# WiFi_Turntable_Controller_v3.net
KiCad netlist of a schematic drawn in EAGLE
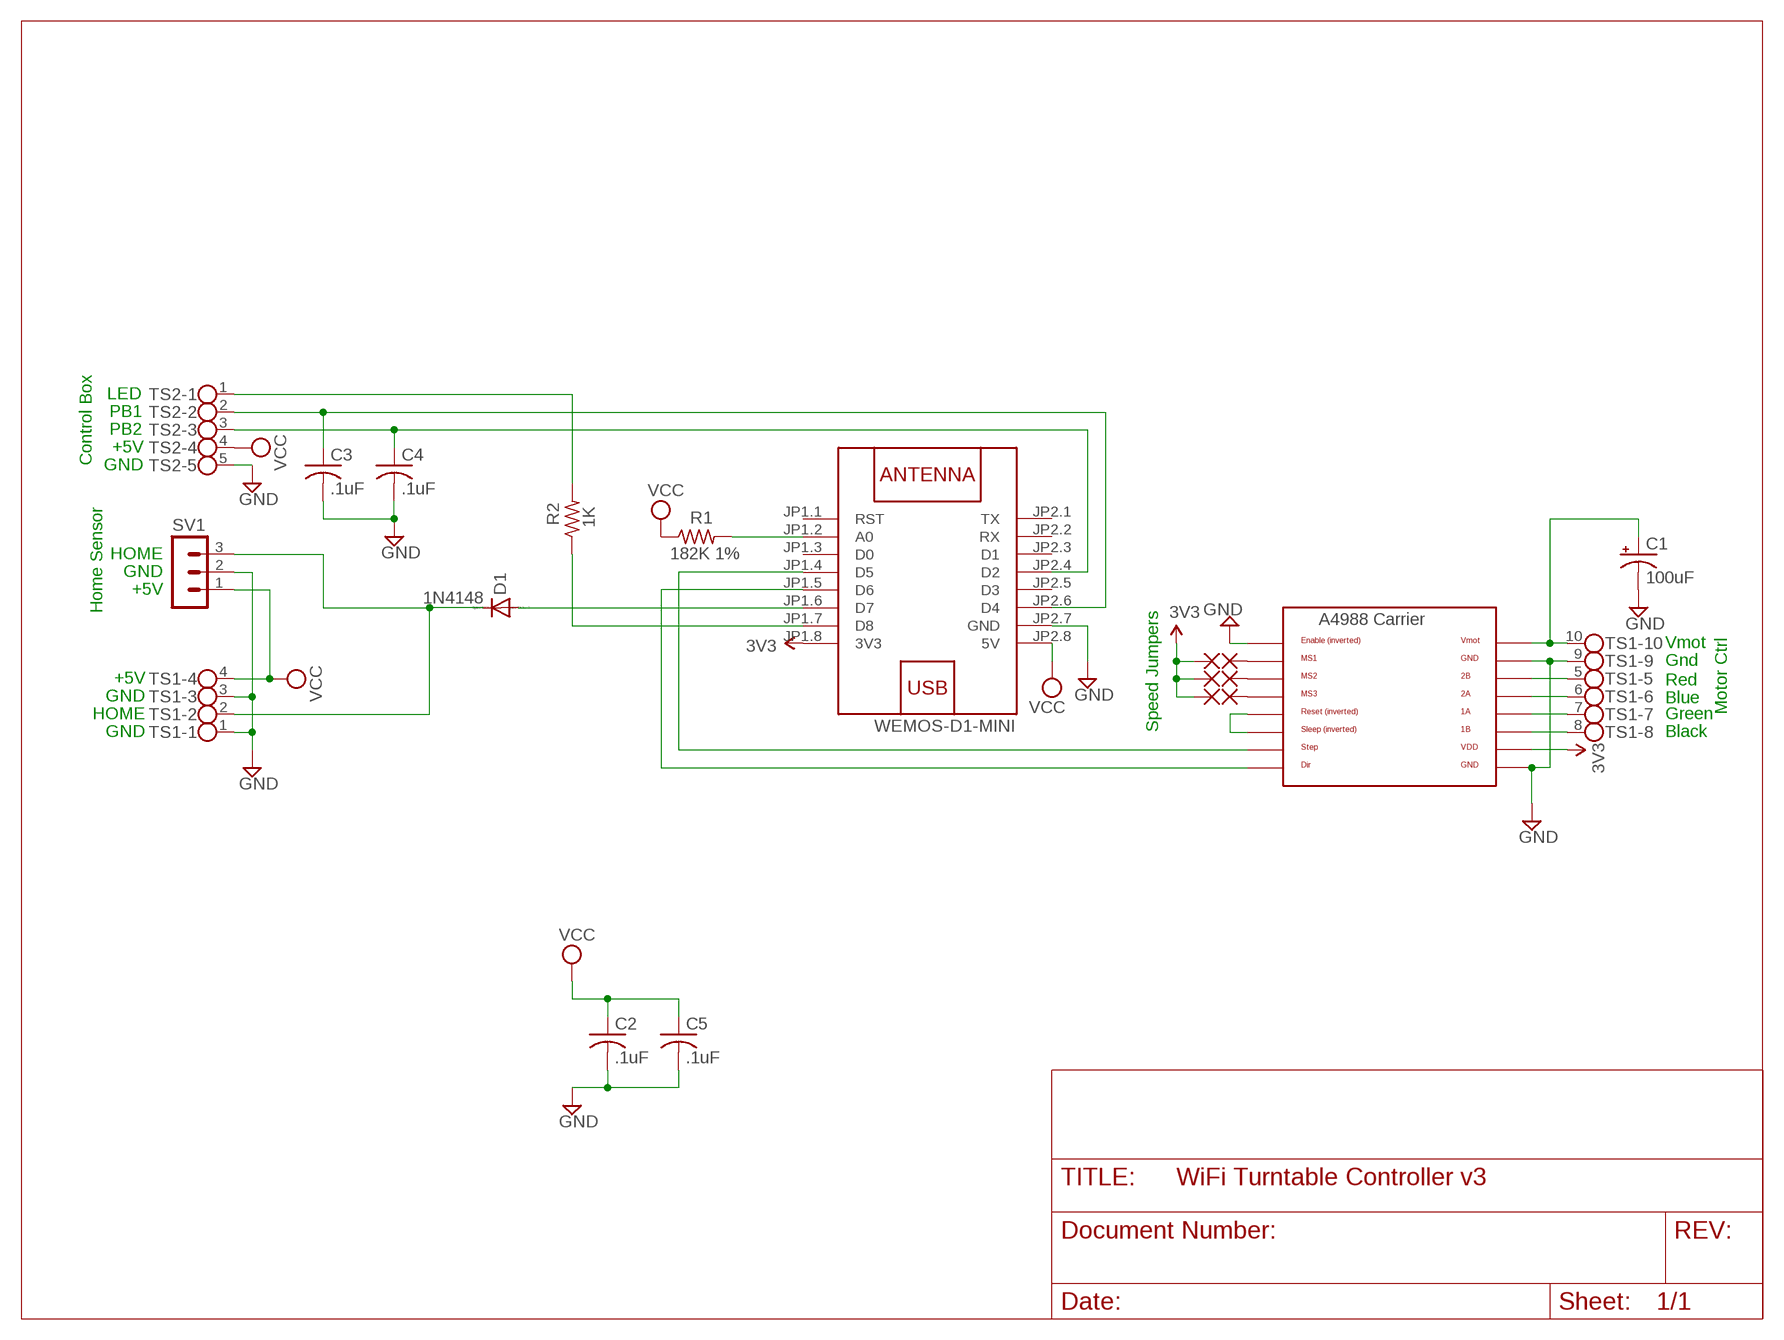
[diagram p0: schematic, sheet 1]

(export (version "E")
  (design (tool "Eeschema 10.0.6"))
  (components
    (comp (ref "C1")
      (value "100uF")
      (footprint "eagle-import:E3,5-8")
      (libsource (lib "eagle-import") (part "CPOL-USE3.5-8"))
    )
    (comp (ref "C2")
      (value ".1uF")
      (footprint "eagle-import:C1206")
      (libsource (lib "eagle-import") (part "C-USC1206"))
    )
    (comp (ref "C3")
      (value ".1uF")
      (footprint "eagle-import:C1206")
      (libsource (lib "eagle-import") (part "C-USC1206"))
    )
    (comp (ref "C4")
      (value ".1uF")
      (footprint "eagle-import:C1206")
      (libsource (lib "eagle-import") (part "C-USC1206"))
    )
    (comp (ref "C5")
      (value ".1uF")
      (footprint "eagle-import:C1206")
      (libsource (lib "eagle-import") (part "C-USC1206"))
    )
    (comp (ref "D1")
      (value "1N4148")
      (footprint "eagle-import:SOD123")
      (libsource (lib "eagle-import") (part "DIODE-SOD123"))
    )
    (comp (ref "PAD1")
      (value "1,6/0,8")
      (footprint "eagle-import:1,6_0,8")
      (libsource (lib "eagle-import") (part "1,6/0,8"))
    )
    (comp (ref "PAD2")
      (value "1,6/0,8")
      (footprint "eagle-import:1,6_0,8")
      (libsource (lib "eagle-import") (part "1,6/0,8"))
    )
    (comp (ref "PAD3")
      (value "1,6/0,8")
      (footprint "eagle-import:1,6_0,8")
      (libsource (lib "eagle-import") (part "1,6/0,8"))
    )
    (comp (ref "PAD4")
      (value "1,6/0,8")
      (footprint "eagle-import:1,6_0,8")
      (libsource (lib "eagle-import") (part "1,6/0,8"))
    )
    (comp (ref "PAD5")
      (value "1,6/0,8")
      (footprint "eagle-import:1,6_0,8")
      (libsource (lib "eagle-import") (part "1,6/0,8"))
    )
    (comp (ref "PAD6")
      (value "1,6/0,8")
      (footprint "eagle-import:1,6_0,8")
      (libsource (lib "eagle-import") (part "1,6/0,8"))
    )
    (comp (ref "R1")
      (value "182K 1%")
      (footprint "eagle-import:R1206")
      (libsource (lib "eagle-import") (part "R-US_R1206"))
    )
    (comp (ref "R2")
      (value "1K")
      (footprint "eagle-import:R1206")
      (libsource (lib "eagle-import") (part "R-US_R1206"))
    )
    (comp (ref "SV1")
      (value "MA03-1")
      (footprint "eagle-import:MA03-1")
      (libsource (lib "eagle-import") (part "MA03-1"))
    )
    (comp (ref "TS1")
      (value "TERMBLK10")
      (footprint "eagle-import:10PB")
      (libsource (lib "eagle-import") (part "TERMBLK10"))
    )
    (comp (ref "TS2")
      (value "TERMBLK05")
      (footprint "eagle-import:05PB")
      (libsource (lib "eagle-import") (part "TERMBLK05"))
    )
    (comp (ref "U$1")
      (value "WEMOS-D1-MINI")
      (footprint "eagle-import:WEMOS-D1-MINI")
      (libsource (lib "eagle-import") (part "WEMOS-D1-MINI"))
    )
    (comp (ref "U$2")
      (value "A4988BREAKOUT")
      (footprint "eagle-import:A4988BREAKOUT")
      (libsource (lib "eagle-import") (part "A4988BREAKOUT"))
    )
  )
  (nets
    (net (code "1") (name "3V3") (class "Default")
      (node (ref "PAD4") (pin "1") (pinfunction "P_1") (pintype "passive"))
      (node (ref "PAD5") (pin "1") (pinfunction "P_1") (pintype "passive"))
      (node (ref "PAD6") (pin "1") (pinfunction "P_1") (pintype "passive"))
      (node (ref "U$1") (pin "JP1.8") (pinfunction "3V3_JP1.8") (pintype "power_in"))
      (node (ref "U$2") (pin "VDD") (pinfunction "VDD_VDD") (pintype "power_in"))
    )
    (net (code "2") (name "GND") (class "Default")
      (node (ref "C1") (pin "-") (pinfunction "-_-") (pintype "passive"))
      (node (ref "C2") (pin "2") (pinfunction "2_2") (pintype "passive"))
      (node (ref "C3") (pin "2") (pinfunction "2_2") (pintype "passive"))
      (node (ref "C4") (pin "2") (pinfunction "2_2") (pintype "passive"))
      (node (ref "C5") (pin "2") (pinfunction "2_2") (pintype "passive"))
      (node (ref "SV1") (pin "2") (pinfunction "2_2") (pintype "passive"))
      (node (ref "TS1") (pin "1") (pinfunction "1_1") (pintype "passive"))
      (node (ref "TS1") (pin "3") (pinfunction "1_3") (pintype "passive"))
      (node (ref "TS1") (pin "9") (pinfunction "1_9") (pintype "passive"))
      (node (ref "TS2") (pin "5") (pinfunction "1_5") (pintype "passive"))
      (node (ref "U$1") (pin "JP2.7") (pinfunction "GND_JP2.7") (pintype "power_in"))
      (node (ref "U$2") (pin "EN") (pinfunction "EN_EN") (pintype "input"))
      (node (ref "U$2") (pin "GND") (pinfunction "GND_GND") (pintype "power_in"))
      (node (ref "U$2") (pin "GND@0") (pinfunction "GND_GND@0") (pintype "power_in"))
    )
    (net (code "3") (name "Net-(PAD1-P)") (class "Default")
      (node (ref "PAD1") (pin "1") (pinfunction "P_1") (pintype "passive"))
      (node (ref "U$2") (pin "MS1") (pinfunction "MS1_MS1") (pintype "input"))
    )
    (net (code "4") (name "Net-(PAD2-P)") (class "Default")
      (node (ref "PAD2") (pin "1") (pinfunction "P_1") (pintype "passive"))
      (node (ref "U$2") (pin "MS2") (pinfunction "MS2_MS2") (pintype "input"))
    )
    (net (code "5") (name "Net-(PAD3-P)") (class "Default")
      (node (ref "PAD3") (pin "1") (pinfunction "P_1") (pintype "passive"))
      (node (ref "U$2") (pin "MS3") (pinfunction "MS3_MS3") (pintype "input"))
    )
    (net (code "6") (name "Net-(R2-Pad2)") (class "Default")
      (node (ref "R2") (pin "2") (pinfunction "2_2") (pintype "passive"))
      (node (ref "TS2") (pin "1") (pinfunction "1_1") (pintype "passive"))
    )
    (net (code "7") (name "Net-(TS1B-1)") (class "Default")
      (node (ref "C1") (pin "+") (pinfunction "+_+") (pintype "passive"))
      (node (ref "TS1") (pin "10") (pinfunction "1_10") (pintype "passive"))
      (node (ref "U$2") (pin "VMOT") (pinfunction "VMOT_VMOT") (pintype "power_in"))
    )
    (net (code "8") (name "Net-(TS1C-1)") (class "Default")
      (node (ref "D1") (pin "C") (pinfunction "C_C") (pintype "passive"))
      (node (ref "SV1") (pin "3") (pinfunction "3_3") (pintype "passive"))
      (node (ref "TS1") (pin "2") (pinfunction "1_2") (pintype "passive"))
    )
    (net (code "9") (name "Net-(TS1F-1)") (class "Default")
      (node (ref "TS1") (pin "5") (pinfunction "1_5") (pintype "passive"))
      (node (ref "U$2") (pin "2B") (pinfunction "2B_2B") (pintype "output"))
    )
    (net (code "10") (name "Net-(TS1G-1)") (class "Default")
      (node (ref "TS1") (pin "6") (pinfunction "1_6") (pintype "passive"))
      (node (ref "U$2") (pin "2A") (pinfunction "2A_2A") (pintype "output"))
    )
    (net (code "11") (name "Net-(TS1H-1)") (class "Default")
      (node (ref "TS1") (pin "7") (pinfunction "1_7") (pintype "passive"))
      (node (ref "U$2") (pin "1A") (pinfunction "1A_1A") (pintype "output"))
    )
    (net (code "12") (name "Net-(TS1I-1)") (class "Default")
      (node (ref "TS1") (pin "8") (pinfunction "1_8") (pintype "passive"))
      (node (ref "U$2") (pin "1B") (pinfunction "1B_1B") (pintype "output"))
    )
    (net (code "13") (name "Net-(TS2B-1)") (class "Default")
      (node (ref "C3") (pin "1") (pinfunction "1_1") (pintype "passive"))
      (node (ref "TS2") (pin "2") (pinfunction "1_2") (pintype "passive"))
      (node (ref "U$1") (pin "JP2.6") (pinfunction "D4_JP2.6") (pintype "bidirectional"))
    )
    (net (code "14") (name "Net-(TS2C-1)") (class "Default")
      (node (ref "C4") (pin "1") (pinfunction "1_1") (pintype "passive"))
      (node (ref "TS2") (pin "3") (pinfunction "1_3") (pintype "passive"))
      (node (ref "U$1") (pin "JP2.4") (pinfunction "D2_JP2.4") (pintype "bidirectional"))
    )
    (net (code "15") (name "Net-(U$1-A0)") (class "Default")
      (node (ref "R1") (pin "2") (pinfunction "2_2") (pintype "passive"))
      (node (ref "U$1") (pin "JP1.2") (pinfunction "A0_JP1.2") (pintype "bidirectional"))
    )
    (net (code "16") (name "Net-(U$1-D5)") (class "Default")
      (node (ref "U$1") (pin "JP1.4") (pinfunction "D5_JP1.4") (pintype "bidirectional"))
      (node (ref "U$2") (pin "STEP") (pinfunction "STEP_STEP") (pintype "input"))
    )
    (net (code "17") (name "Net-(U$1-D6)") (class "Default")
      (node (ref "U$1") (pin "JP1.5") (pinfunction "D6_JP1.5") (pintype "bidirectional"))
      (node (ref "U$2") (pin "DIR") (pinfunction "DIR_DIR") (pintype "input"))
    )
    (net (code "18") (name "Net-(U$1-D7)") (class "Default")
      (node (ref "D1") (pin "A") (pinfunction "A_A") (pintype "passive"))
      (node (ref "U$1") (pin "JP1.6") (pinfunction "D7_JP1.6") (pintype "bidirectional"))
    )
    (net (code "19") (name "Net-(U$1-D8)") (class "Default")
      (node (ref "R2") (pin "1") (pinfunction "1_1") (pintype "passive"))
      (node (ref "U$1") (pin "JP1.7") (pinfunction "D8_JP1.7") (pintype "bidirectional"))
    )
    (net (code "20") (name "Net-(U$2-SLEEP)") (class "Default")
      (node (ref "U$2") (pin "RST") (pinfunction "RST_RST") (pintype "input"))
      (node (ref "U$2") (pin "SLP") (pinfunction "SLEEP_SLP") (pintype "input"))
    )
    (net (code "21") (name "VCC") (class "Default")
      (node (ref "C2") (pin "1") (pinfunction "1_1") (pintype "passive"))
      (node (ref "C5") (pin "1") (pinfunction "1_1") (pintype "passive"))
      (node (ref "R1") (pin "1") (pinfunction "1_1") (pintype "passive"))
      (node (ref "SV1") (pin "1") (pinfunction "1_1") (pintype "passive"))
      (node (ref "TS1") (pin "4") (pinfunction "1_4") (pintype "passive"))
      (node (ref "TS2") (pin "4") (pinfunction "1_4") (pintype "passive"))
      (node (ref "U$1") (pin "JP2.8") (pinfunction "5V_JP2.8") (pintype "power_in"))
    )
    (net (code "22") (name "unconnected-(U$1-D0-PadJP1.3)") (class "Default")
      (node (ref "U$1") (pin "JP1.3") (pinfunction "D0_JP1.3") (pintype "bidirectional"))
    )
    (net (code "23") (name "unconnected-(U$1-D1-PadJP2.3)") (class "Default")
      (node (ref "U$1") (pin "JP2.3") (pinfunction "D1_JP2.3") (pintype "bidirectional"))
    )
    (net (code "24") (name "unconnected-(U$1-D3-PadJP2.5)") (class "Default")
      (node (ref "U$1") (pin "JP2.5") (pinfunction "D3_JP2.5") (pintype "bidirectional"))
    )
    (net (code "25") (name "unconnected-(U$1-RST-PadJP1.1)") (class "Default")
      (node (ref "U$1") (pin "JP1.1") (pinfunction "RST_JP1.1") (pintype "bidirectional"))
    )
    (net (code "26") (name "unconnected-(U$1-RX-PadJP2.2)") (class "Default")
      (node (ref "U$1") (pin "JP2.2") (pinfunction "RX_JP2.2") (pintype "bidirectional"))
    )
    (net (code "27") (name "unconnected-(U$1-TX-PadJP2.1)") (class "Default")
      (node (ref "U$1") (pin "JP2.1") (pinfunction "TX_JP2.1") (pintype "bidirectional"))
    )
  )
)
